# Module_A_IO.net
KiCad netlist of a schematic drawn in Altium Designer
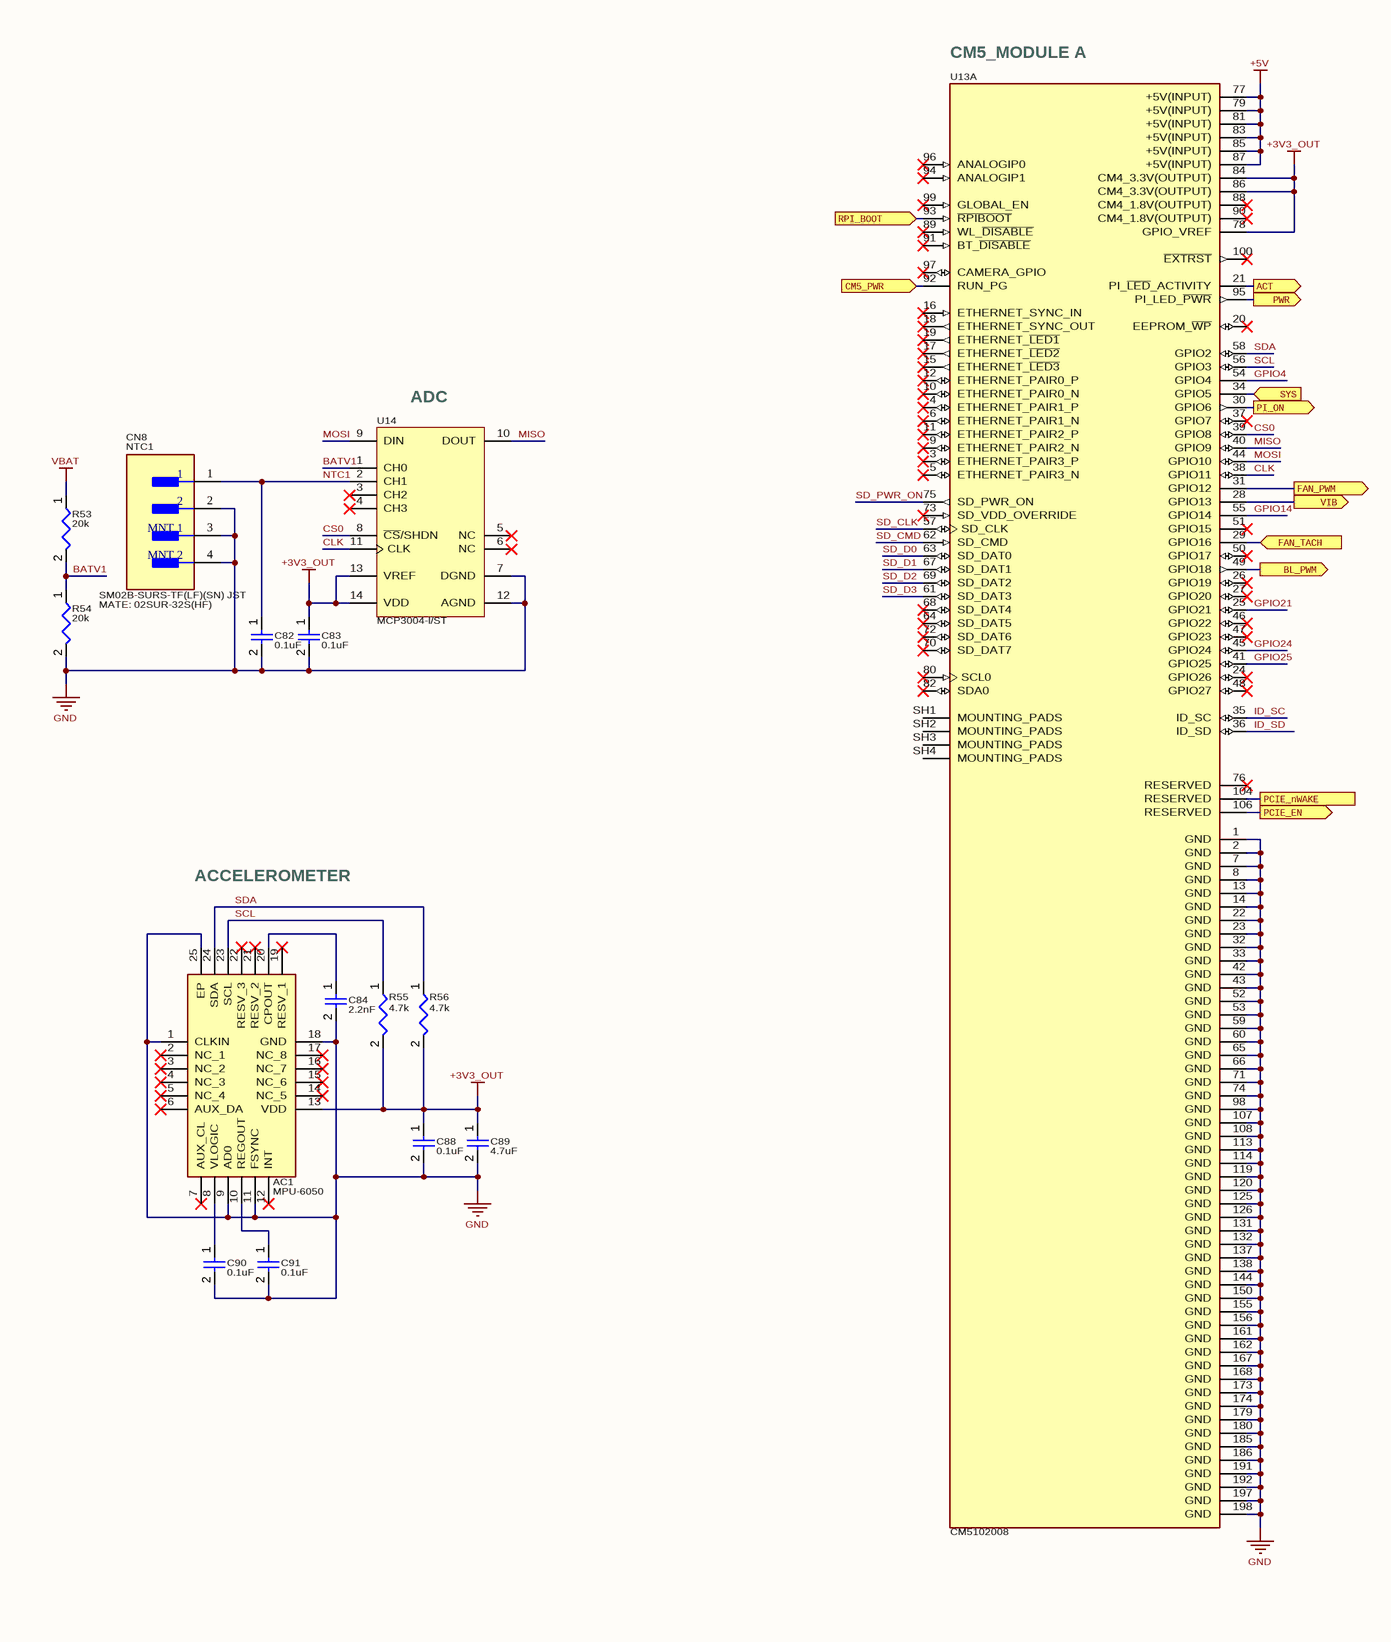
[diagram p0: Module A IO.SchDoc, left]
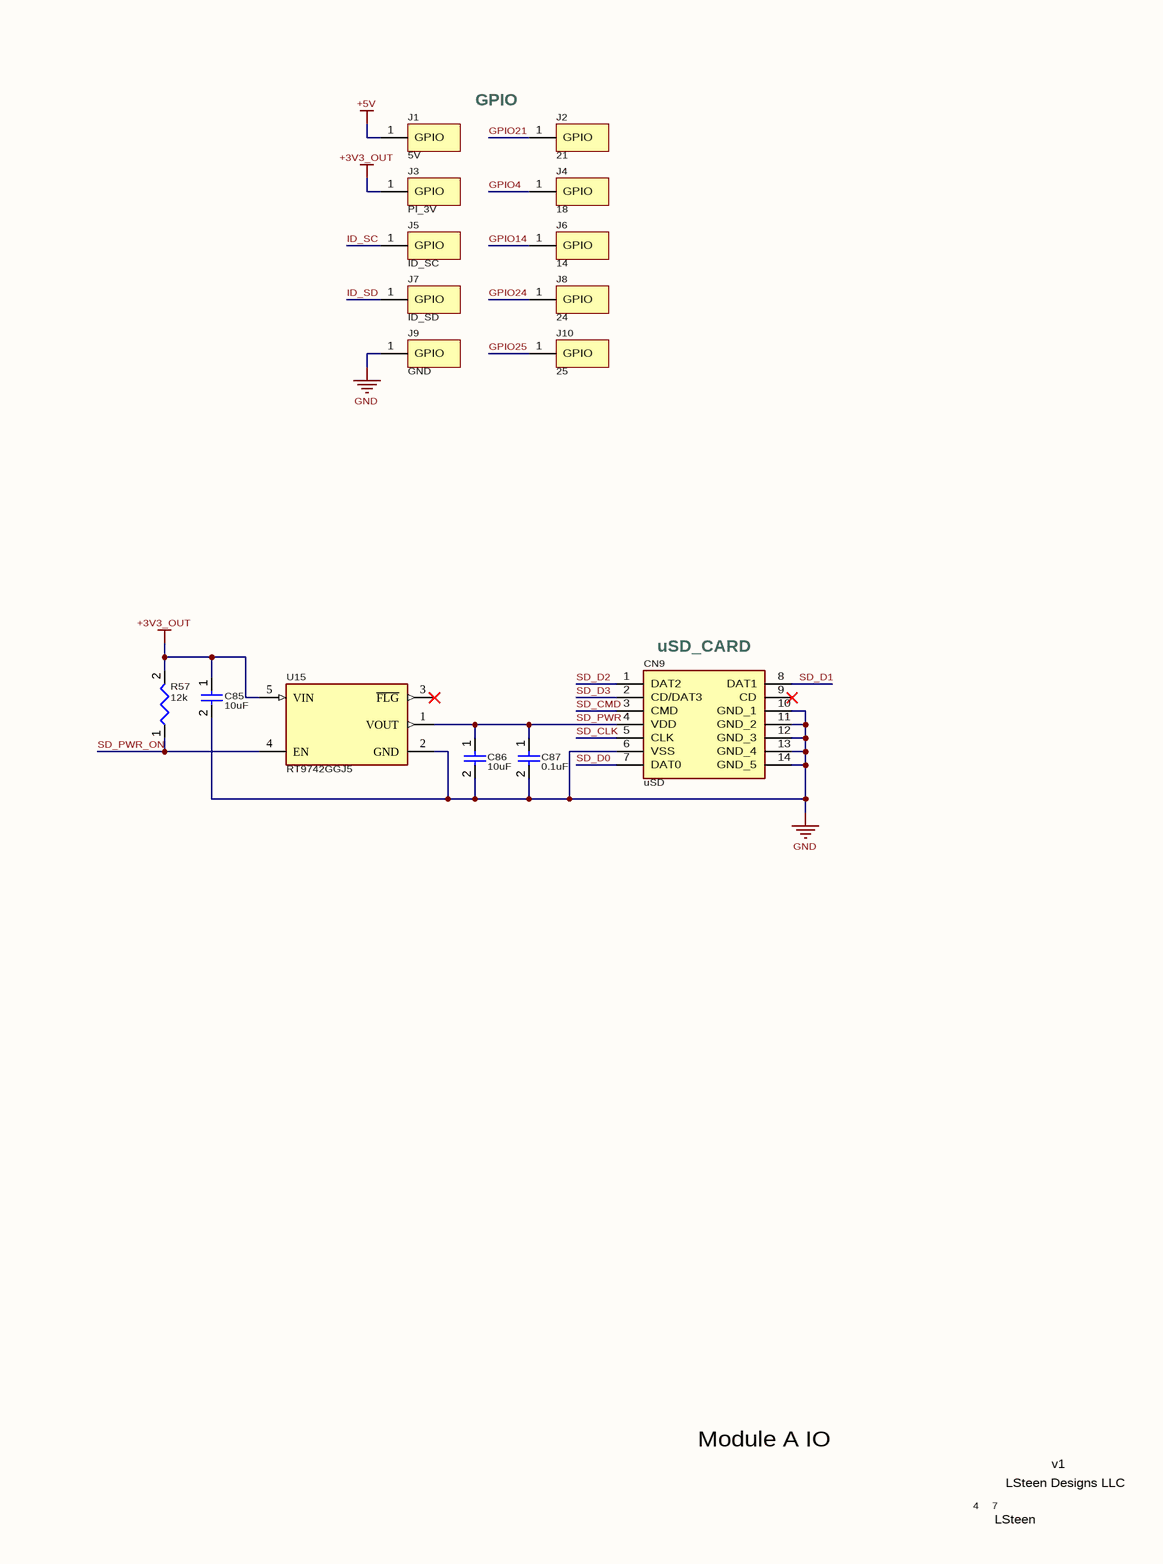
[diagram p1: Module A IO.SchDoc, right]

(export (version "E")
  (design (tool "Eeschema 10.0.6"))
  (components
    (comp (ref "AC1")
      (value "MPU-6050")
      (footprint "SamacSys:MPU6050")
      (description "Integrated Circuit")
      (fields (field (name "MOUSER PART NUMBER") "410-MPU-6050"))
      (libsource (lib "SamacSys") (part "MPU-6050"))
    )
    (comp (ref "C82")
      (value "0.1uF")
      (footprint "CAPC1005X56X25LL10T15")
      (description "Chip Capacitor, 0.1 uF, +/- 5%, 16 V, 0402 (1005 Metric)")
      (fields (field (name "TOLERANCE") "5%"))
      (libsource (lib "Colorado Technical University") (part "CAP-NP-2"))
    )
    (comp (ref "C83")
      (value "0.1uF")
      (footprint "CAPC1005X56X25LL10T15")
      (description "Chip Capacitor, 0.1 uF, +/- 5%, 16 V, 0402 (1005 Metric)")
      (fields (field (name "TOLERANCE") "5%"))
      (libsource (lib "Colorado Technical University") (part "CAP-NP-2"))
    )
    (comp (ref "C84")
      (value "2.2nF")
      (footprint "CAPC1005X56X25LL10T15")
      (description "Chip Capacitor, 2.2nF, +/- 5%, 16 V, 0402 (1005 Metric)")
      (fields (field (name "TOLERANCE") "5%"))
      (libsource (lib "Colorado Technical University") (part "CAP-NP-2"))
    )
    (comp (ref "C85")
      (value "10uF")
      (footprint "CAPC0603(1608)100_L")
      (description "Chip Capacitor, 10uF +/-20%, 10V, 0603, Thickness 1 mm")
      (fields (field (name "TOLERANCE") "10%"))
      (libsource (lib "Colorado Technical University") (part "CAP-NP-2"))
    )
    (comp (ref "C86")
      (value "10uF")
      (footprint "CAPC0603(1608)100_L")
      (description "Chip Capacitor, 10uF +/-20%, 10V, 0603, Thickness 1 mm")
      (fields (field (name "TOLERANCE") "10%"))
      (libsource (lib "Colorado Technical University") (part "CAP-NP-2"))
    )
    (comp (ref "C87")
      (value "0.1uF")
      (footprint "CAPC1005X56X25LL10T15")
      (description "Chip Capacitor, 0.1 uF, +/- 5%, 16 V, 0402 (1005 Metric)")
      (fields (field (name "TOLERANCE") "5%"))
      (libsource (lib "Colorado Technical University") (part "CAP-NP-2"))
    )
    (comp (ref "C88")
      (value "0.1uF")
      (footprint "CAPC1005X56X25LL10T15")
      (description "Chip Capacitor, 0.1 uF, +/- 5%, 16 V, 0402 (1005 Metric)")
      (fields (field (name "TOLERANCE") "5%"))
      (libsource (lib "Colorado Technical University") (part "CAP-NP-2"))
    )
    (comp (ref "C89")
      (value "4.7uF")
      (footprint "CAPC0603(1608)100_L")
      (description "Chip Capacitor, 4.7uF +/-20%, 10V, 0603, Thickness 1 mm")
      (fields (field (name "TOLERANCE") "10%"))
      (libsource (lib "Colorado Technical University") (part "CAP-NP-2"))
    )
    (comp (ref "C90")
      (value "0.1uF")
      (footprint "CAPC1005X56X25LL10T15")
      (description "Chip Capacitor, 0.1 uF, +/- 5%, 16 V, 0402 (1005 Metric)")
      (fields (field (name "TOLERANCE") "5%"))
      (libsource (lib "Colorado Technical University") (part "CAP-NP-2"))
    )
    (comp (ref "C91")
      (value "0.1uF")
      (footprint "CAPC1005X56X25LL10T15")
      (description "Chip Capacitor, 0.1 uF, +/- 5%, 16 V, 0402 (1005 Metric)")
      (fields (field (name "TOLERANCE") "5%"))
      (libsource (lib "Colorado Technical University") (part "CAP-NP-2"))
    )
    (comp (ref "CN8")
      (value "NTC1")
      (footprint "FP-SM02B-SURS-TF_LF_SN-MFG")
      (description "LCSC_CONN HEADER SMD R/A 2POS 0.8MM")
      (libsource (lib "Altium Content Vault") (part "6ebc6fc72a9fd5a6899c7600f385cff"))
    )
    (comp (ref "CN9")
      (value "uSD")
      (footprint "SamacSys:MSD9A")
      (description "Connector")
      (fields (field (name "MANUFACTURER_PART_NUMBER") "MSD-9-A"))
      (libsource (lib "SamacSys") (part "MSD-9-A"))
    )
    (comp (ref "J1")
      (value "5V")
      (footprint "GPIO")
      (description "AUX_I/O")
      (libsource (lib "Schlib1") (part "GPIO"))
    )
    (comp (ref "J2")
      (value "21")
      (footprint "GPIO")
      (description "AUX_I/O")
      (libsource (lib "Schlib1") (part "GPIO"))
    )
    (comp (ref "J3")
      (value "PI_3V")
      (footprint "GPIO")
      (description "AUX_I/O")
      (libsource (lib "Schlib1") (part "GPIO"))
    )
    (comp (ref "J4")
      (value "18")
      (footprint "GPIO")
      (description "AUX_I/O")
      (libsource (lib "Schlib1") (part "GPIO"))
    )
    (comp (ref "J5")
      (value "ID_SC")
      (footprint "GPIO")
      (description "AUX_I/O")
      (libsource (lib "Schlib1") (part "GPIO"))
    )
    (comp (ref "J6")
      (value "14")
      (footprint "GPIO")
      (description "AUX_I/O")
      (libsource (lib "Schlib1") (part "GPIO"))
    )
    (comp (ref "J7")
      (value "ID_SD")
      (footprint "GPIO")
      (description "AUX_I/O")
      (libsource (lib "Schlib1") (part "GPIO"))
    )
    (comp (ref "J8")
      (value "24")
      (footprint "GPIO")
      (description "AUX_I/O")
      (libsource (lib "Schlib1") (part "GPIO"))
    )
    (comp (ref "J9")
      (value "GND")
      (footprint "GPIO")
      (description "AUX_I/O")
      (libsource (lib "Schlib1") (part "GPIO"))
    )
    (comp (ref "J10")
      (value "25")
      (footprint "GPIO")
      (description "AUX_I/O")
      (libsource (lib "Schlib1") (part "GPIO"))
    )
    (comp (ref "R53")
      (value "20k")
      (footprint "RESC0402(1005)_L")
      (description "Chip Resistor, 20 kOhms, +/-5 %, 63 mW, -55 to 155 degC, 0402")
      (fields (field (name "TOLERANCE") "5%") (field (name "POWER") "63mW"))
      (libsource (lib "Colorado Technical University") (part "RES-2"))
    )
    (comp (ref "R54")
      (value "20k")
      (footprint "RESC0402(1005)_L")
      (description "Chip Resistor, 20 kOhms, +/-5 %, 63 mW, -55 to 155 degC, 0402")
      (fields (field (name "TOLERANCE") "5%") (field (name "POWER") "63mW"))
      (libsource (lib "Colorado Technical University") (part "RES-2"))
    )
    (comp (ref "R55")
      (value "4.7k")
      (footprint "RESC0402(1005)_L")
      (description "Chip Resistor, 4.7 kOhms, +/-5 %, 63 mW, -55 to 155 degC, 0402")
      (fields (field (name "TOLERANCE") "5%") (field (name "POWER") "63mW"))
      (libsource (lib "Colorado Technical University") (part "RES-2"))
    )
    (comp (ref "R56")
      (value "4.7k")
      (footprint "RESC0402(1005)_L")
      (description "Chip Resistor, 4.7 kOhms, +/-5 %, 63 mW, -55 to 155 degC, 0402")
      (fields (field (name "TOLERANCE") "5%") (field (name "POWER") "63mW"))
      (libsource (lib "Colorado Technical University") (part "RES-2"))
    )
    (comp (ref "R57")
      (value "12k")
      (footprint "RESC0402(1005)_L")
      (description "Chip Resistor, 12 kOhms, +/-5 %, 63 mW, -55 to 155 degC, 0402")
      (fields (field (name "TOLERANCE") "5%") (field (name "POWER") "63mW"))
      (libsource (lib "Colorado Technical University") (part "RES-2"))
    )
    (comp (ref "U13")
      (value "CM5102008")
      (footprint "MODULE_CM4102008")
      (description "Raspberry Pi Compute Module 4 with WiFi 2GB RAM 8GB Flash ¦ Raspberry Pi CM4102008")
      (fields (field (name "MF") "Raspberry Pi") (field (name "MP") "CM4102008"))
      (libsource (lib "CM4102008") (part "CM4102008"))
    )
    (comp (ref "U14")
      (value "MCP3004-I/ST")
      (footprint "TSSOP-ST14_M")
      (libsource (lib "Altium Content Vault") (part "CON-ADC-MCP3004-14"))
    )
    (comp (ref "U15")
      (value "RT9742GGJ5")
      (footprint "FP-RT9742GGJ5-IPC_C")
      (description "IC PWR SWTCH N-CHAN 1:1 TSOT23-5")
      (libsource (lib "Altium Content Vault") (part "6b3db7b45087fee8fb60b49bef92a32"))
    )
  )
  (nets
    (net (code "1") (name "+3V3_OUT") (class "Default")
      (node (ref "AC1") (pin "13") (pinfunction "VDD_13") (pintype "passive"))
      (node (ref "C83") (pin "1") (pinfunction "1_1") (pintype "passive"))
      (node (ref "C85") (pin "1") (pinfunction "1_1") (pintype "passive"))
      (node (ref "C88") (pin "1") (pinfunction "1_1") (pintype "passive"))
      (node (ref "C89") (pin "1") (pinfunction "1_1") (pintype "passive"))
      (node (ref "J3") (pin "1") (pinfunction "GPIO_1") (pintype "passive"))
      (node (ref "R55") (pin "2") (pinfunction "2_2") (pintype "passive"))
      (node (ref "R56") (pin "2") (pinfunction "2_2") (pintype "passive"))
      (node (ref "R57") (pin "2") (pinfunction "2_2") (pintype "passive"))
      (node (ref "U13") (pin "78") (pinfunction "GPIO_VREF_78") (pintype "power_in"))
      (node (ref "U13") (pin "84") (pinfunction "CM4_3.3V(OUTPUT)_84") (pintype "power_in"))
      (node (ref "U13") (pin "86") (pinfunction "CM4_3.3V(OUTPUT)_86") (pintype "power_in"))
      (node (ref "U14") (pin "13") (pinfunction "VREF_13") (pintype "passive"))
      (node (ref "U14") (pin "14") (pinfunction "VDD_14") (pintype "power_in"))
      (node (ref "U15") (pin "5") (pinfunction "VIN_5") (pintype "input"))
    )
    (net (code "2") (name "+5V") (class "Default")
      (node (ref "J1") (pin "1") (pinfunction "GPIO_1") (pintype "passive"))
      (node (ref "U13") (pin "77") (pinfunction "+5V(INPUT)_77") (pintype "power_in"))
      (node (ref "U13") (pin "79") (pinfunction "+5V(INPUT)_79") (pintype "power_in"))
      (node (ref "U13") (pin "81") (pinfunction "+5V(INPUT)_81") (pintype "power_in"))
      (node (ref "U13") (pin "83") (pinfunction "+5V(INPUT)_83") (pintype "power_in"))
      (node (ref "U13") (pin "85") (pinfunction "+5V(INPUT)_85") (pintype "power_in"))
      (node (ref "U13") (pin "87") (pinfunction "+5V(INPUT)_87") (pintype "power_in"))
    )
    (net (code "3") (name "/ACT") (class "Default")
      (node (ref "U13") (pin "21") (pinfunction "PI_~{LED}_ACTIVITY_21") (pintype "passive"))
    )
    (net (code "4") (name "/BATV1") (class "Default")
      (node (ref "R53") (pin "2") (pinfunction "2_2") (pintype "passive"))
      (node (ref "R54") (pin "1") (pinfunction "1_1") (pintype "passive"))
      (node (ref "U14") (pin "1") (pinfunction "CH0_1") (pintype "passive"))
    )
    (net (code "5") (name "/BL_PWM") (class "Default")
      (node (ref "U13") (pin "49") (pinfunction "GPIO18_49") (pintype "output"))
    )
    (net (code "6") (name "/CLK") (class "Default")
      (node (ref "U13") (pin "38") (pinfunction "GPIO11_38") (pintype "bidirectional"))
      (node (ref "U14") (pin "11") (pinfunction "CLK_11") (pintype "passive"))
    )
    (net (code "7") (name "/CM5_PWR") (class "Default")
      (node (ref "U13") (pin "92") (pinfunction "RUN_PG_92") (pintype "passive"))
    )
    (net (code "8") (name "/CS0") (class "Default")
      (node (ref "U13") (pin "39") (pinfunction "GPIO8_39") (pintype "bidirectional"))
      (node (ref "U14") (pin "8") (pinfunction "~{CS}/SHDN_8") (pintype "passive"))
    )
    (net (code "9") (name "/FAN_PWM") (class "Default")
      (node (ref "U13") (pin "31") (pinfunction "GPIO12_31") (pintype "passive"))
    )
    (net (code "10") (name "/FAN_TACH") (class "Default")
      (node (ref "U13") (pin "29") (pinfunction "GPIO16_29") (pintype "passive"))
    )
    (net (code "11") (name "/GPIO4") (class "Default")
      (node (ref "J4") (pin "1") (pinfunction "GPIO_1") (pintype "passive"))
      (node (ref "U13") (pin "54") (pinfunction "GPIO4_54") (pintype "passive"))
    )
    (net (code "12") (name "/GPIO14") (class "Default")
      (node (ref "J6") (pin "1") (pinfunction "GPIO_1") (pintype "passive"))
      (node (ref "U13") (pin "55") (pinfunction "GPIO14_55") (pintype "passive"))
    )
    (net (code "13") (name "/GPIO21") (class "Default")
      (node (ref "J2") (pin "1") (pinfunction "GPIO_1") (pintype "passive"))
      (node (ref "U13") (pin "25") (pinfunction "GPIO21_25") (pintype "bidirectional"))
    )
    (net (code "14") (name "/GPIO24") (class "Default")
      (node (ref "J8") (pin "1") (pinfunction "GPIO_1") (pintype "passive"))
      (node (ref "U13") (pin "45") (pinfunction "GPIO24_45") (pintype "bidirectional"))
    )
    (net (code "15") (name "/GPIO25") (class "Default")
      (node (ref "J10") (pin "1") (pinfunction "GPIO_1") (pintype "passive"))
      (node (ref "U13") (pin "41") (pinfunction "GPIO25_41") (pintype "bidirectional"))
    )
    (net (code "16") (name "/ID_SC") (class "Default")
      (node (ref "J5") (pin "1") (pinfunction "GPIO_1") (pintype "passive"))
      (node (ref "U13") (pin "35") (pinfunction "ID_SC_35") (pintype "bidirectional"))
    )
    (net (code "17") (name "/ID_SD") (class "Default")
      (node (ref "J7") (pin "1") (pinfunction "GPIO_1") (pintype "passive"))
      (node (ref "U13") (pin "36") (pinfunction "ID_SD_36") (pintype "bidirectional"))
    )
    (net (code "18") (name "/MISO") (class "Default")
      (node (ref "U13") (pin "40") (pinfunction "GPIO9_40") (pintype "bidirectional"))
      (node (ref "U14") (pin "10") (pinfunction "DOUT_10") (pintype "tri_state"))
    )
    (net (code "19") (name "/MOSI") (class "Default")
      (node (ref "U13") (pin "44") (pinfunction "GPIO10_44") (pintype "bidirectional"))
      (node (ref "U14") (pin "9") (pinfunction "DIN_9") (pintype "passive"))
    )
    (net (code "20") (name "/NTC1") (class "Default")
      (node (ref "C82") (pin "1") (pinfunction "1_1") (pintype "passive"))
      (node (ref "CN8") (pin "1") (pinfunction "1_1") (pintype "passive"))
      (node (ref "U14") (pin "2") (pinfunction "CH1_2") (pintype "passive"))
    )
    (net (code "21") (name "/PCIE_EN") (class "Default")
      (node (ref "U13") (pin "106") (pinfunction "RESERVED_106") (pintype "passive"))
    )
    (net (code "22") (name "/PCIE_nWAKE") (class "Default")
      (node (ref "U13") (pin "104") (pinfunction "RESERVED_104") (pintype "passive"))
    )
    (net (code "23") (name "/PI_ON") (class "Default")
      (node (ref "U13") (pin "30") (pinfunction "GPIO6_30") (pintype "output"))
    )
    (net (code "24") (name "/PWR") (class "Default")
      (node (ref "U13") (pin "95") (pinfunction "PI_LED_~{PWR}_95") (pintype "output"))
    )
    (net (code "25") (name "/RPI_BOOT") (class "Default")
      (node (ref "U13") (pin "93") (pinfunction "~{RPIBOOT}_93") (pintype "input"))
    )
    (net (code "26") (name "/SCL") (class "Default")
      (node (ref "AC1") (pin "23") (pinfunction "SCL_23") (pintype "passive"))
      (node (ref "R55") (pin "1") (pinfunction "1_1") (pintype "passive"))
      (node (ref "U13") (pin "56") (pinfunction "GPIO3_56") (pintype "bidirectional"))
    )
    (net (code "27") (name "/SDA") (class "Default")
      (node (ref "AC1") (pin "24") (pinfunction "SDA_24") (pintype "passive"))
      (node (ref "R56") (pin "1") (pinfunction "1_1") (pintype "passive"))
      (node (ref "U13") (pin "58") (pinfunction "GPIO2_58") (pintype "bidirectional"))
    )
    (net (code "28") (name "/SD_CLK") (class "Default")
      (node (ref "CN9") (pin "5") (pinfunction "CLK_5") (pintype "passive"))
      (node (ref "U13") (pin "57") (pinfunction "SD_CLK_57") (pintype "bidirectional"))
    )
    (net (code "29") (name "/SD_CMD") (class "Default")
      (node (ref "CN9") (pin "3") (pinfunction "CMD_3") (pintype "passive"))
      (node (ref "U13") (pin "62") (pinfunction "SD_CMD_62") (pintype "input"))
    )
    (net (code "30") (name "/SD_D0") (class "Default")
      (node (ref "CN9") (pin "7") (pinfunction "DAT0_7") (pintype "passive"))
      (node (ref "U13") (pin "63") (pinfunction "SD_DAT0_63") (pintype "bidirectional"))
    )
    (net (code "31") (name "/SD_D1") (class "Default")
      (node (ref "CN9") (pin "8") (pinfunction "DAT1_8") (pintype "passive"))
      (node (ref "U13") (pin "67") (pinfunction "SD_DAT1_67") (pintype "bidirectional"))
    )
    (net (code "32") (name "/SD_D2") (class "Default")
      (node (ref "CN9") (pin "1") (pinfunction "DAT2_1") (pintype "passive"))
      (node (ref "U13") (pin "69") (pinfunction "SD_DAT2_69") (pintype "bidirectional"))
    )
    (net (code "33") (name "/SD_D3") (class "Default")
      (node (ref "CN9") (pin "2") (pinfunction "CD/DAT3_2") (pintype "passive"))
      (node (ref "U13") (pin "61") (pinfunction "SD_DAT3_61") (pintype "bidirectional"))
    )
    (net (code "34") (name "/SD_PWR") (class "Default")
      (node (ref "C86") (pin "1") (pinfunction "1_1") (pintype "passive"))
      (node (ref "C87") (pin "1") (pinfunction "1_1") (pintype "passive"))
      (node (ref "CN9") (pin "4") (pinfunction "VDD_4") (pintype "passive"))
      (node (ref "U15") (pin "1") (pinfunction "VOUT_1") (pintype "output"))
    )
    (net (code "35") (name "/SD_PWR_ON") (class "Default")
      (node (ref "R57") (pin "1") (pinfunction "1_1") (pintype "passive"))
      (node (ref "U13") (pin "75") (pinfunction "SD_PWR_ON_75") (pintype "output"))
      (node (ref "U15") (pin "4") (pinfunction "EN_4") (pintype "passive"))
    )
    (net (code "36") (name "/SYS") (class "Default")
      (node (ref "U13") (pin "34") (pinfunction "GPIO5_34") (pintype "passive"))
    )
    (net (code "37") (name "/VIB") (class "Default")
      (node (ref "U13") (pin "28") (pinfunction "GPIO13_28") (pintype "passive"))
    )
    (net (code "38") (name "GND") (class "Default")
      (node (ref "AC1") (pin "1") (pinfunction "CLKIN_1") (pintype "passive"))
      (node (ref "AC1") (pin "11") (pinfunction "FSYNC_11") (pintype "passive"))
      (node (ref "AC1") (pin "18") (pinfunction "GND_18") (pintype "passive"))
      (node (ref "AC1") (pin "25") (pinfunction "EP_25") (pintype "passive"))
      (node (ref "AC1") (pin "9") (pinfunction "AD0_9") (pintype "passive"))
      (node (ref "C82") (pin "2") (pinfunction "2_2") (pintype "passive"))
      (node (ref "C83") (pin "2") (pinfunction "2_2") (pintype "passive"))
      (node (ref "C84") (pin "2") (pinfunction "2_2") (pintype "passive"))
      (node (ref "C85") (pin "2") (pinfunction "2_2") (pintype "passive"))
      (node (ref "C86") (pin "2") (pinfunction "2_2") (pintype "passive"))
      (node (ref "C87") (pin "2") (pinfunction "2_2") (pintype "passive"))
      (node (ref "C88") (pin "2") (pinfunction "2_2") (pintype "passive"))
      (node (ref "C89") (pin "2") (pinfunction "2_2") (pintype "passive"))
      (node (ref "C90") (pin "2") (pinfunction "2_2") (pintype "passive"))
      (node (ref "C91") (pin "2") (pinfunction "2_2") (pintype "passive"))
      (node (ref "CN8") (pin "2") (pinfunction "2_2") (pintype "passive"))
      (node (ref "CN8") (pin "3") (pinfunction "MNT_1_3") (pintype "passive"))
      (node (ref "CN8") (pin "4") (pinfunction "MNT_2_4") (pintype "passive"))
      (node (ref "CN9") (pin "10") (pinfunction "GND_1_10") (pintype "passive"))
      (node (ref "CN9") (pin "11") (pinfunction "GND_2_11") (pintype "passive"))
      (node (ref "CN9") (pin "12") (pinfunction "GND_3_12") (pintype "passive"))
      (node (ref "CN9") (pin "13") (pinfunction "GND_4_13") (pintype "passive"))
      (node (ref "CN9") (pin "14") (pinfunction "GND_5_14") (pintype "passive"))
      (node (ref "CN9") (pin "6") (pinfunction "VSS_6") (pintype "passive"))
      (node (ref "J9") (pin "1") (pinfunction "GPIO_1") (pintype "passive"))
      (node (ref "R54") (pin "2") (pinfunction "2_2") (pintype "passive"))
      (node (ref "U13") (pin "1") (pinfunction "GND_1") (pintype "power_in"))
      (node (ref "U13") (pin "107") (pinfunction "GND_107") (pintype "power_in"))
      (node (ref "U13") (pin "108") (pinfunction "GND_108") (pintype "power_in"))
      (node (ref "U13") (pin "113") (pinfunction "GND_113") (pintype "power_in"))
      (node (ref "U13") (pin "114") (pinfunction "GND_114") (pintype "power_in"))
      (node (ref "U13") (pin "119") (pinfunction "GND_119") (pintype "power_in"))
      (node (ref "U13") (pin "120") (pinfunction "GND_120") (pintype "power_in"))
      (node (ref "U13") (pin "125") (pinfunction "GND_125") (pintype "power_in"))
      (node (ref "U13") (pin "126") (pinfunction "GND_126") (pintype "power_in"))
      (node (ref "U13") (pin "13") (pinfunction "GND_13") (pintype "power_in"))
      (node (ref "U13") (pin "131") (pinfunction "GND_131") (pintype "power_in"))
      (node (ref "U13") (pin "132") (pinfunction "GND_132") (pintype "power_in"))
      (node (ref "U13") (pin "137") (pinfunction "GND_137") (pintype "power_in"))
      (node (ref "U13") (pin "138") (pinfunction "GND_138") (pintype "power_in"))
      (node (ref "U13") (pin "14") (pinfunction "GND_14") (pintype "power_in"))
      (node (ref "U13") (pin "144") (pinfunction "GND_144") (pintype "power_in"))
      (node (ref "U13") (pin "150") (pinfunction "GND_150") (pintype "power_in"))
      (node (ref "U13") (pin "155") (pinfunction "GND_155") (pintype "power_in"))
      (node (ref "U13") (pin "156") (pinfunction "GND_156") (pintype "power_in"))
      (node (ref "U13") (pin "161") (pinfunction "GND_161") (pintype "power_in"))
      (node (ref "U13") (pin "162") (pinfunction "GND_162") (pintype "power_in"))
      (node (ref "U13") (pin "167") (pinfunction "GND_167") (pintype "power_in"))
      (node (ref "U13") (pin "168") (pinfunction "GND_168") (pintype "power_in"))
      (node (ref "U13") (pin "173") (pinfunction "GND_173") (pintype "power_in"))
      (node (ref "U13") (pin "174") (pinfunction "GND_174") (pintype "power_in"))
      (node (ref "U13") (pin "179") (pinfunction "GND_179") (pintype "power_in"))
      (node (ref "U13") (pin "180") (pinfunction "GND_180") (pintype "power_in"))
      (node (ref "U13") (pin "185") (pinfunction "GND_185") (pintype "power_in"))
      (node (ref "U13") (pin "186") (pinfunction "GND_186") (pintype "power_in"))
      (node (ref "U13") (pin "191") (pinfunction "GND_191") (pintype "power_in"))
      (node (ref "U13") (pin "192") (pinfunction "GND_192") (pintype "power_in"))
      (node (ref "U13") (pin "197") (pinfunction "GND_197") (pintype "power_in"))
      (node (ref "U13") (pin "198") (pinfunction "GND_198") (pintype "power_in"))
      (node (ref "U13") (pin "2") (pinfunction "GND_2") (pintype "power_in"))
      (node (ref "U13") (pin "22") (pinfunction "GND_22") (pintype "power_in"))
      (node (ref "U13") (pin "23") (pinfunction "GND_23") (pintype "power_in"))
      (node (ref "U13") (pin "32") (pinfunction "GND_32") (pintype "power_in"))
      (node (ref "U13") (pin "33") (pinfunction "GND_33") (pintype "power_in"))
      (node (ref "U13") (pin "42") (pinfunction "GND_42") (pintype "power_in"))
      (node (ref "U13") (pin "43") (pinfunction "GND_43") (pintype "power_in"))
      (node (ref "U13") (pin "52") (pinfunction "GND_52") (pintype "power_in"))
      (node (ref "U13") (pin "53") (pinfunction "GND_53") (pintype "power_in"))
      (node (ref "U13") (pin "59") (pinfunction "GND_59") (pintype "power_in"))
      (node (ref "U13") (pin "60") (pinfunction "GND_60") (pintype "power_in"))
      (node (ref "U13") (pin "65") (pinfunction "GND_65") (pintype "power_in"))
      (node (ref "U13") (pin "66") (pinfunction "GND_66") (pintype "power_in"))
      (node (ref "U13") (pin "7") (pinfunction "GND_7") (pintype "power_in"))
      (node (ref "U13") (pin "71") (pinfunction "GND_71") (pintype "power_in"))
      (node (ref "U13") (pin "74") (pinfunction "GND_74") (pintype "power_in"))
      (node (ref "U13") (pin "8") (pinfunction "GND_8") (pintype "power_in"))
      (node (ref "U13") (pin "98") (pinfunction "GND_98") (pintype "power_in"))
      (node (ref "U14") (pin "12") (pinfunction "AGND_12") (pintype "power_in"))
      (node (ref "U14") (pin "7") (pinfunction "DGND_7") (pintype "power_in"))
      (node (ref "U15") (pin "2") (pinfunction "GND_2") (pintype "power_in"))
    )
    (net (code "39") (name "Net-(AC1-CPOUT)") (class "Default")
      (node (ref "AC1") (pin "20") (pinfunction "CPOUT_20") (pintype "passive"))
      (node (ref "C84") (pin "1") (pinfunction "1_1") (pintype "passive"))
    )
    (net (code "40") (name "Net-(AC1-REGOUT)") (class "Default")
      (node (ref "AC1") (pin "10") (pinfunction "REGOUT_10") (pintype "passive"))
      (node (ref "C91") (pin "1") (pinfunction "1_1") (pintype "passive"))
    )
    (net (code "41") (name "Net-(AC1-VLOGIC)") (class "Default")
      (node (ref "AC1") (pin "8") (pinfunction "VLOGIC_8") (pintype "passive"))
      (node (ref "C90") (pin "1") (pinfunction "1_1") (pintype "passive"))
    )
    (net (code "42") (name "VBAT") (class "Default")
      (node (ref "R53") (pin "1") (pinfunction "1_1") (pintype "passive"))
    )
    (net (code "43") (name "unconnected-(AC1-AUX_CL-Pad7)") (class "Default")
      (node (ref "AC1") (pin "7") (pinfunction "AUX_CL_7") (pintype "passive+no_connect"))
    )
    (net (code "44") (name "unconnected-(AC1-AUX_DA-Pad6)") (class "Default")
      (node (ref "AC1") (pin "6") (pinfunction "AUX_DA_6") (pintype "passive+no_connect"))
    )
    (net (code "45") (name "unconnected-(AC1-INT-Pad12)") (class "Default")
      (node (ref "AC1") (pin "12") (pinfunction "INT_12") (pintype "passive+no_connect"))
    )
    (net (code "46") (name "unconnected-(AC1-NC_1-Pad2)") (class "Default")
      (node (ref "AC1") (pin "2") (pinfunction "NC_1_2") (pintype "passive+no_connect"))
    )
    (net (code "47") (name "unconnected-(AC1-NC_2-Pad3)") (class "Default")
      (node (ref "AC1") (pin "3") (pinfunction "NC_2_3") (pintype "passive+no_connect"))
    )
    (net (code "48") (name "unconnected-(AC1-NC_3-Pad4)") (class "Default")
      (node (ref "AC1") (pin "4") (pinfunction "NC_3_4") (pintype "passive+no_connect"))
    )
    (net (code "49") (name "unconnected-(AC1-NC_4-Pad5)") (class "Default")
      (node (ref "AC1") (pin "5") (pinfunction "NC_4_5") (pintype "passive+no_connect"))
    )
    (net (code "50") (name "unconnected-(AC1-NC_5-Pad14)") (class "Default")
      (node (ref "AC1") (pin "14") (pinfunction "NC_5_14") (pintype "passive+no_connect"))
    )
    (net (code "51") (name "unconnected-(AC1-NC_6-Pad15)") (class "Default")
      (node (ref "AC1") (pin "15") (pinfunction "NC_6_15") (pintype "passive+no_connect"))
    )
    (net (code "52") (name "unconnected-(AC1-NC_7-Pad16)") (class "Default")
      (node (ref "AC1") (pin "16") (pinfunction "NC_7_16") (pintype "passive+no_connect"))
    )
    (net (code "53") (name "unconnected-(AC1-NC_8-Pad17)") (class "Default")
      (node (ref "AC1") (pin "17") (pinfunction "NC_8_17") (pintype "passive+no_connect"))
    )
    (net (code "54") (name "unconnected-(AC1-RESV_1-Pad19)") (class "Default")
      (node (ref "AC1") (pin "19") (pinfunction "RESV_1_19") (pintype "passive+no_connect"))
    )
    (net (code "55") (name "unconnected-(AC1-RESV_2-Pad21)") (class "Default")
      (node (ref "AC1") (pin "21") (pinfunction "RESV_2_21") (pintype "passive+no_connect"))
    )
    (net (code "56") (name "unconnected-(AC1-RESV_3-Pad22)") (class "Default")
      (node (ref "AC1") (pin "22") (pinfunction "RESV_3_22") (pintype "passive+no_connect"))
    )
    (net (code "57") (name "unconnected-(CN9-CD-Pad9)") (class "Default")
      (node (ref "CN9") (pin "9") (pinfunction "CD_9") (pintype "passive+no_connect"))
    )
    (net (code "58") (name "unconnected-(U13A-ANALOGIP0-Pad96)") (class "Default")
      (node (ref "U13") (pin "96") (pinfunction "ANALOGIP0_96") (pintype "input+no_connect"))
    )
    (net (code "59") (name "unconnected-(U13A-ANALOGIP1-Pad94)") (class "Default")
      (node (ref "U13") (pin "94") (pinfunction "ANALOGIP1_94") (pintype "input+no_connect"))
    )
    (net (code "60") (name "unconnected-(U13A-BT_~{DISABLE}-Pad91)") (class "Default")
      (node (ref "U13") (pin "91") (pinfunction "BT_~{DISABLE}_91") (pintype "input+no_connect"))
    )
    (net (code "61") (name "unconnected-(U13A-CAMERA_GPIO-Pad97)") (class "Default")
      (node (ref "U13") (pin "97") (pinfunction "CAMERA_GPIO_97") (pintype "bidirectional+no_connect"))
    )
    (net (code "62") (name "unconnected-(U13A-CM4_1.8V(OUTPUT)-Pad88)") (class "Default")
      (node (ref "U13") (pin "88") (pinfunction "CM4_1.8V(OUTPUT)_88") (pintype "power_in+no_connect"))
    )
    (net (code "63") (name "unconnected-(U13A-CM4_1.8V(OUTPUT)-Pad90)") (class "Default")
      (node (ref "U13") (pin "90") (pinfunction "CM4_1.8V(OUTPUT)_90") (pintype "power_in+no_connect"))
    )
    (net (code "64") (name "unconnected-(U13A-EEPROM_~{WP}-Pad20)") (class "Default")
      (node (ref "U13") (pin "20") (pinfunction "EEPROM_~{WP}_20") (pintype "bidirectional+no_connect"))
    )
    (net (code "65") (name "unconnected-(U13A-ETHERNET_PAIR0_N-Pad10)") (class "Default")
      (node (ref "U13") (pin "10") (pinfunction "ETHERNET_PAIR0_N_10") (pintype "bidirectional+no_connect"))
    )
    (net (code "66") (name "unconnected-(U13A-ETHERNET_PAIR0_P-Pad12)") (class "Default")
      (node (ref "U13") (pin "12") (pinfunction "ETHERNET_PAIR0_P_12") (pintype "bidirectional+no_connect"))
    )
    (net (code "67") (name "unconnected-(U13A-ETHERNET_PAIR1_N-Pad6)") (class "Default")
      (node (ref "U13") (pin "6") (pinfunction "ETHERNET_PAIR1_N_6") (pintype "bidirectional+no_connect"))
    )
    (net (code "68") (name "unconnected-(U13A-ETHERNET_PAIR1_P-Pad4)") (class "Default")
      (node (ref "U13") (pin "4") (pinfunction "ETHERNET_PAIR1_P_4") (pintype "bidirectional+no_connect"))
    )
    (net (code "69") (name "unconnected-(U13A-ETHERNET_PAIR2_N-Pad9)") (class "Default")
      (node (ref "U13") (pin "9") (pinfunction "ETHERNET_PAIR2_N_9") (pintype "bidirectional+no_connect"))
    )
    (net (code "70") (name "unconnected-(U13A-ETHERNET_PAIR2_P-Pad11)") (class "Default")
      (node (ref "U13") (pin "11") (pinfunction "ETHERNET_PAIR2_P_11") (pintype "bidirectional+no_connect"))
    )
    (net (code "71") (name "unconnected-(U13A-ETHERNET_PAIR3_N-Pad5)") (class "Default")
      (node (ref "U13") (pin "5") (pinfunction "ETHERNET_PAIR3_N_5") (pintype "bidirectional+no_connect"))
    )
    (net (code "72") (name "unconnected-(U13A-ETHERNET_PAIR3_P-Pad3)") (class "Default")
      (node (ref "U13") (pin "3") (pinfunction "ETHERNET_PAIR3_P_3") (pintype "bidirectional+no_connect"))
    )
    (net (code "73") (name "unconnected-(U13A-ETHERNET_SYNC_IN-Pad16)") (class "Default")
      (node (ref "U13") (pin "16") (pinfunction "ETHERNET_SYNC_IN_16") (pintype "input+no_connect"))
    )
    (net (code "74") (name "unconnected-(U13A-ETHERNET_SYNC_OUT-Pad18)") (class "Default")
      (node (ref "U13") (pin "18") (pinfunction "ETHERNET_SYNC_OUT_18") (pintype "output+no_connect"))
    )
    (net (code "75") (name "unconnected-(U13A-ETHERNET_~{LED1}-Pad19)") (class "Default")
      (node (ref "U13") (pin "19") (pinfunction "ETHERNET_~{LED1}_19") (pintype "output+no_connect"))
    )
    (net (code "76") (name "unconnected-(U13A-ETHERNET_~{LED2}-Pad17)") (class "Default")
      (node (ref "U13") (pin "17") (pinfunction "ETHERNET_~{LED2}_17") (pintype "output+no_connect"))
    )
    (net (code "77") (name "unconnected-(U13A-ETHERNET_~{LED3}-Pad15)") (class "Default")
      (node (ref "U13") (pin "15") (pinfunction "ETHERNET_~{LED3}_15") (pintype "output+no_connect"))
    )
    (net (code "78") (name "unconnected-(U13A-GLOBAL_EN-Pad99)") (class "Default")
      (node (ref "U13") (pin "99") (pinfunction "GLOBAL_EN_99") (pintype "input+no_connect"))
    )
    (net (code "79") (name "unconnected-(U13A-GPIO7-Pad37)") (class "Default")
      (node (ref "U13") (pin "37") (pinfunction "GPIO7_37") (pintype "bidirectional+no_connect"))
    )
    (net (code "80") (name "unconnected-(U13A-GPIO15-Pad51)") (class "Default")
      (node (ref "U13") (pin "51") (pinfunction "GPIO15_51") (pintype "passive+no_connect"))
    )
    (net (code "81") (name "unconnected-(U13A-GPIO17-Pad50)") (class "Default")
      (node (ref "U13") (pin "50") (pinfunction "GPIO17_50") (pintype "bidirectional+no_connect"))
    )
    (net (code "82") (name "unconnected-(U13A-GPIO19-Pad26)") (class "Default")
      (node (ref "U13") (pin "26") (pinfunction "GPIO19_26") (pintype "bidirectional+no_connect"))
    )
    (net (code "83") (name "unconnected-(U13A-GPIO20-Pad27)") (class "Default")
      (node (ref "U13") (pin "27") (pinfunction "GPIO20_27") (pintype "bidirectional+no_connect"))
    )
    (net (code "84") (name "unconnected-(U13A-GPIO22-Pad46)") (class "Default")
      (node (ref "U13") (pin "46") (pinfunction "GPIO22_46") (pintype "bidirectional+no_connect"))
    )
    (net (code "85") (name "unconnected-(U13A-GPIO23-Pad47)") (class "Default")
      (node (ref "U13") (pin "47") (pinfunction "GPIO23_47") (pintype "bidirectional+no_connect"))
    )
    (net (code "86") (name "unconnected-(U13A-GPIO26-Pad24)") (class "Default")
      (node (ref "U13") (pin "24") (pinfunction "GPIO26_24") (pintype "bidirectional+no_connect"))
    )
    (net (code "87") (name "unconnected-(U13A-GPIO27-Pad48)") (class "Default")
      (node (ref "U13") (pin "48") (pinfunction "GPIO27_48") (pintype "bidirectional+no_connect"))
    )
    (net (code "88") (name "unconnected-(U13A-MOUNTING_PADS-PadSH1)") (class "Default")
      (node (ref "U13") (pin "SH1") (pinfunction "MOUNTING_PADS_SH1") (pintype "passive"))
    )
    (net (code "89") (name "unconnected-(U13A-MOUNTING_PADS-PadSH2)") (class "Default")
      (node (ref "U13") (pin "SH2") (pinfunction "MOUNTING_PADS_SH2") (pintype "passive"))
    )
    (net (code "90") (name "unconnected-(U13A-MOUNTING_PADS-PadSH3)") (class "Default")
      (node (ref "U13") (pin "SH3") (pinfunction "MOUNTING_PADS_SH3") (pintype "passive"))
    )
    (net (code "91") (name "unconnected-(U13A-MOUNTING_PADS-PadSH4)") (class "Default")
      (node (ref "U13") (pin "SH4") (pinfunction "MOUNTING_PADS_SH4") (pintype "passive"))
    )
    (net (code "92") (name "unconnected-(U13A-RESERVED-Pad76)") (class "Default")
      (node (ref "U13") (pin "76") (pinfunction "RESERVED_76") (pintype "passive+no_connect"))
    )
    (net (code "93") (name "unconnected-(U13A-SCL0-Pad80)") (class "Default")
      (node (ref "U13") (pin "80") (pinfunction "SCL0_80") (pintype "input+no_connect"))
    )
    (net (code "94") (name "unconnected-(U13A-SDA0-Pad82)") (class "Default")
      (node (ref "U13") (pin "82") (pinfunction "SDA0_82") (pintype "bidirectional+no_connect"))
    )
    (net (code "95") (name "unconnected-(U13A-SD_DAT4-Pad68)") (class "Default")
      (node (ref "U13") (pin "68") (pinfunction "SD_DAT4_68") (pintype "bidirectional+no_connect"))
    )
    (net (code "96") (name "unconnected-(U13A-SD_DAT5-Pad64)") (class "Default")
      (node (ref "U13") (pin "64") (pinfunction "SD_DAT5_64") (pintype "bidirectional+no_connect"))
    )
    (net (code "97") (name "unconnected-(U13A-SD_DAT6-Pad72)") (class "Default")
      (node (ref "U13") (pin "72") (pinfunction "SD_DAT6_72") (pintype "bidirectional+no_connect"))
    )
    (net (code "98") (name "unconnected-(U13A-SD_DAT7-Pad70)") (class "Default")
      (node (ref "U13") (pin "70") (pinfunction "SD_DAT7_70") (pintype "bidirectional+no_connect"))
    )
    (net (code "99") (name "unconnected-(U13A-SD_VDD_OVERRIDE-Pad73)") (class "Default")
      (node (ref "U13") (pin "73") (pinfunction "SD_VDD_OVERRIDE_73") (pintype "input+no_connect"))
    )
    (net (code "100") (name "unconnected-(U13A-WL_~{DISABLE}-Pad89)") (class "Default")
      (node (ref "U13") (pin "89") (pinfunction "WL_~{DISABLE}_89") (pintype "input+no_connect"))
    )
    (net (code "101") (name "unconnected-(U13A-~{EXTRST}-Pad100)") (class "Default")
      (node (ref "U13") (pin "100") (pinfunction "~{EXTRST}_100") (pintype "output+no_connect"))
    )
    (net (code "102") (name "unconnected-(U14-CH2-Pad3)") (class "Default")
      (node (ref "U14") (pin "3") (pinfunction "CH2_3") (pintype "passive+no_connect"))
    )
    (net (code "103") (name "unconnected-(U14-CH3-Pad4)") (class "Default")
      (node (ref "U14") (pin "4") (pinfunction "CH3_4") (pintype "passive+no_connect"))
    )
    (net (code "104") (name "unconnected-(U14-NC-Pad5)") (class "Default")
      (node (ref "U14") (pin "5") (pinfunction "NC_5") (pintype "passive+no_connect"))
    )
    (net (code "105") (name "unconnected-(U14-NC-Pad6)") (class "Default")
      (node (ref "U14") (pin "6") (pinfunction "NC_6") (pintype "passive+no_connect"))
    )
    (net (code "106") (name "unconnected-(U15-~{FLG}-Pad3)") (class "Default")
      (node (ref "U15") (pin "3") (pinfunction "~{FLG}_3") (pintype "output+no_connect"))
    )
  )
)
